# RX_slim.net
KiCad netlist of a schematic drawn in EAGLE
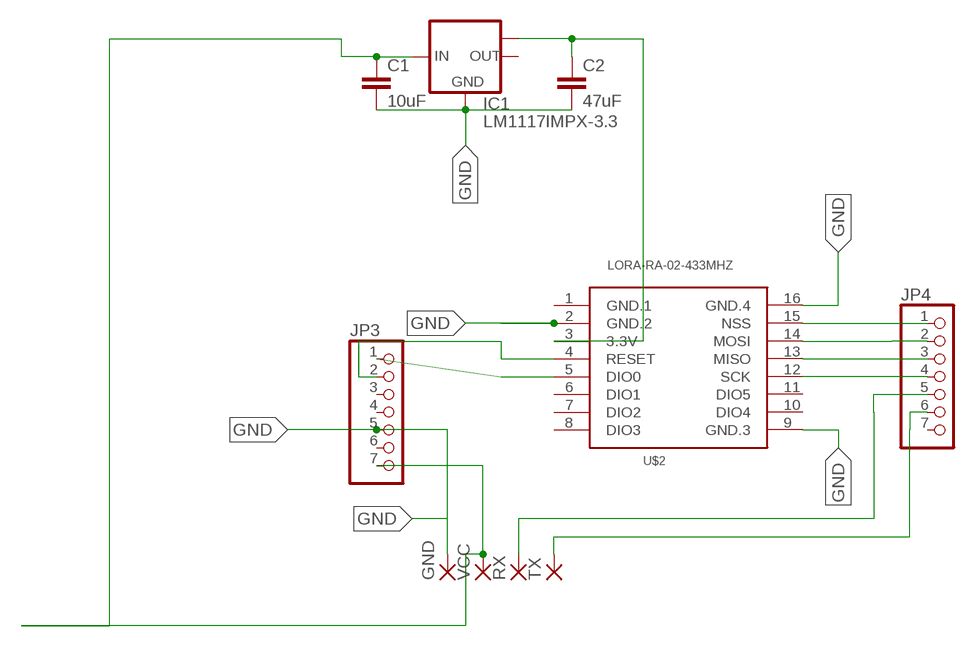
[diagram p0: schematic, sheet 1]

(export (version "E")
  (design (tool "Eeschema 10.0.6"))
  (components
    (comp (ref "C1")
      (value "10uF")
      (footprint "eagle-import:0805")
      (libsource (lib "eagle-import") (part "0.33UF/330NF-0805-50V-10%"))
    )
    (comp (ref "C2")
      (value "47uF")
      (footprint "eagle-import:0805")
      (libsource (lib "eagle-import") (part "0.33UF/330NF-0805-50V-10%"))
    )
    (comp (ref "GND")
      (value "SMD2")
      (footprint "eagle-import:SMD1,27-2,54")
      (libsource (lib "eagle-import") (part "SMD2"))
    )
    (comp (ref "IC1")
      (value "LM1117IMPX-3.3")
      (footprint "eagle-import:SOT223")
      (libsource (lib "eagle-import") (part "LM1117IMPX-3.3"))
    )
    (comp (ref "JP3")
      (value "PINHD-1X7")
      (footprint "eagle-import:1X07")
      (libsource (lib "eagle-import") (part "PINHD-1X7"))
    )
    (comp (ref "JP4")
      (value "PINHD-1X7")
      (footprint "eagle-import:1X07")
      (libsource (lib "eagle-import") (part "PINHD-1X7"))
    )
    (comp (ref "RX")
      (value "SMD2")
      (footprint "eagle-import:SMD1,27-2,54")
      (libsource (lib "eagle-import") (part "SMD2"))
    )
    (comp (ref "TX")
      (value "SMD2")
      (footprint "eagle-import:SMD1,27-2,54")
      (libsource (lib "eagle-import") (part "SMD2"))
    )
    (comp (ref "U$2")
      (value "LORA-RA-02-433MHZ")
      (footprint "eagle-import:LORA-RA2-SMD")
      (fields (field (name "SPICEPREFIX") "X"))
      (libsource (lib "eagle-import") (part "LORA-RA-02-433MHZ"))
    )
    (comp (ref "VCC")
      (value "SMD2")
      (footprint "eagle-import:SMD1,27-2,54")
      (libsource (lib "eagle-import") (part "SMD2"))
    )
  )
  (nets
    (net (code "1") (name "/GND.1") (class "Default")
      (node (ref "U$2") (pin "1") (pinfunction "GND.1_1") (pintype "power_in"))
    )
    (net (code "2") (name "GND") (class "Default")
      (node (ref "C1") (pin "2") (pinfunction "2_2") (pintype "passive"))
      (node (ref "C2") (pin "2") (pinfunction "2_2") (pintype "passive"))
      (node (ref "GND") (pin "1") (pinfunction "P_1") (pintype "passive"))
      (node (ref "IC1") (pin "1") (pinfunction "GND_1") (pintype "input"))
      (node (ref "JP3") (pin "5") (pinfunction "5_5") (pintype "passive"))
      (node (ref "U$2") (pin "16") (pinfunction "GND.4_16") (pintype "power_in"))
      (node (ref "U$2") (pin "2") (pinfunction "GND.2_2") (pintype "power_in"))
      (node (ref "U$2") (pin "9") (pinfunction "GND.3_9") (pintype "power_in"))
    )
    (net (code "3") (name "Net-(IC1-IN)") (class "Default")
      (node (ref "C1") (pin "1") (pinfunction "1_1") (pintype "passive"))
      (node (ref "IC1") (pin "3") (pinfunction "IN_3") (pintype "input"))
      (node (ref "JP3") (pin "7") (pinfunction "7_7") (pintype "passive"))
      (node (ref "VCC") (pin "1") (pinfunction "P_1") (pintype "passive"))
    )
    (net (code "4") (name "Net-(IC1-OUT1)") (class "Default")
      (node (ref "C2") (pin "1") (pinfunction "1_1") (pintype "passive"))
      (node (ref "IC1") (pin "TAB") (pinfunction "OUT1_TAB") (pintype "passive"))
      (node (ref "U$2") (pin "3") (pinfunction "3.3V_3") (pintype "power_in"))
    )
    (net (code "5") (name "Net-(RX-P)") (class "Default")
      (node (ref "JP4") (pin "5") (pinfunction "5_5") (pintype "passive"))
      (node (ref "RX") (pin "1") (pinfunction "P_1") (pintype "passive"))
    )
    (net (code "6") (name "Net-(TX-P)") (class "Default")
      (node (ref "JP4") (pin "6") (pinfunction "6_6") (pintype "passive"))
      (node (ref "TX") (pin "1") (pinfunction "P_1") (pintype "passive"))
    )
    (net (code "7") (name "Net-(U$2-DIO0)") (class "Default")
      (node (ref "JP3") (pin "1") (pinfunction "1_1") (pintype "passive"))
      (node (ref "U$2") (pin "5") (pinfunction "DIO0_5") (pintype "bidirectional"))
    )
    (net (code "8") (name "Net-(U$2-MISO)") (class "Default")
      (node (ref "JP4") (pin "3") (pinfunction "3_3") (pintype "passive"))
      (node (ref "U$2") (pin "13") (pinfunction "MISO_13") (pintype "bidirectional"))
    )
    (net (code "9") (name "Net-(U$2-MOSI)") (class "Default")
      (node (ref "JP4") (pin "2") (pinfunction "2_2") (pintype "passive"))
      (node (ref "U$2") (pin "14") (pinfunction "MOSI_14") (pintype "bidirectional"))
    )
    (net (code "10") (name "Net-(U$2-NSS)") (class "Default")
      (node (ref "JP4") (pin "1") (pinfunction "1_1") (pintype "passive"))
      (node (ref "U$2") (pin "15") (pinfunction "NSS_15") (pintype "bidirectional"))
    )
    (net (code "11") (name "Net-(U$2-RESET)") (class "Default")
      (node (ref "JP3") (pin "2") (pinfunction "2_2") (pintype "passive"))
      (node (ref "U$2") (pin "4") (pinfunction "RESET_4") (pintype "bidirectional"))
    )
    (net (code "12") (name "Net-(U$2-SCK)") (class "Default")
      (node (ref "JP4") (pin "4") (pinfunction "4_4") (pintype "passive"))
      (node (ref "U$2") (pin "12") (pinfunction "SCK_12") (pintype "bidirectional"))
    )
    (net (code "13") (name "unconnected-(IC1-OUT-Pad2)") (class "Default")
      (node (ref "IC1") (pin "2") (pinfunction "OUT_2") (pintype "passive"))
    )
    (net (code "14") (name "unconnected-(JP3-Pad3)") (class "Default")
      (node (ref "JP3") (pin "3") (pinfunction "3_3") (pintype "passive"))
    )
    (net (code "15") (name "unconnected-(JP3-Pad4)") (class "Default")
      (node (ref "JP3") (pin "4") (pinfunction "4_4") (pintype "passive"))
    )
    (net (code "16") (name "unconnected-(JP3-Pad6)") (class "Default")
      (node (ref "JP3") (pin "6") (pinfunction "6_6") (pintype "passive"))
    )
    (net (code "17") (name "unconnected-(JP4-Pad7)") (class "Default")
      (node (ref "JP4") (pin "7") (pinfunction "7_7") (pintype "passive"))
    )
    (net (code "18") (name "unconnected-(U$2-DIO1-Pad6)") (class "Default")
      (node (ref "U$2") (pin "6") (pinfunction "DIO1_6") (pintype "bidirectional"))
    )
    (net (code "19") (name "unconnected-(U$2-DIO2-Pad7)") (class "Default")
      (node (ref "U$2") (pin "7") (pinfunction "DIO2_7") (pintype "bidirectional"))
    )
    (net (code "20") (name "unconnected-(U$2-DIO3-Pad8)") (class "Default")
      (node (ref "U$2") (pin "8") (pinfunction "DIO3_8") (pintype "bidirectional"))
    )
    (net (code "21") (name "unconnected-(U$2-DIO4-Pad10)") (class "Default")
      (node (ref "U$2") (pin "10") (pinfunction "DIO4_10") (pintype "bidirectional"))
    )
    (net (code "22") (name "unconnected-(U$2-DIO5-Pad11)") (class "Default")
      (node (ref "U$2") (pin "11") (pinfunction "DIO5_11") (pintype "bidirectional"))
    )
  )
)
